# PIPduino.net
KiCad netlist of a schematic drawn in EAGLE
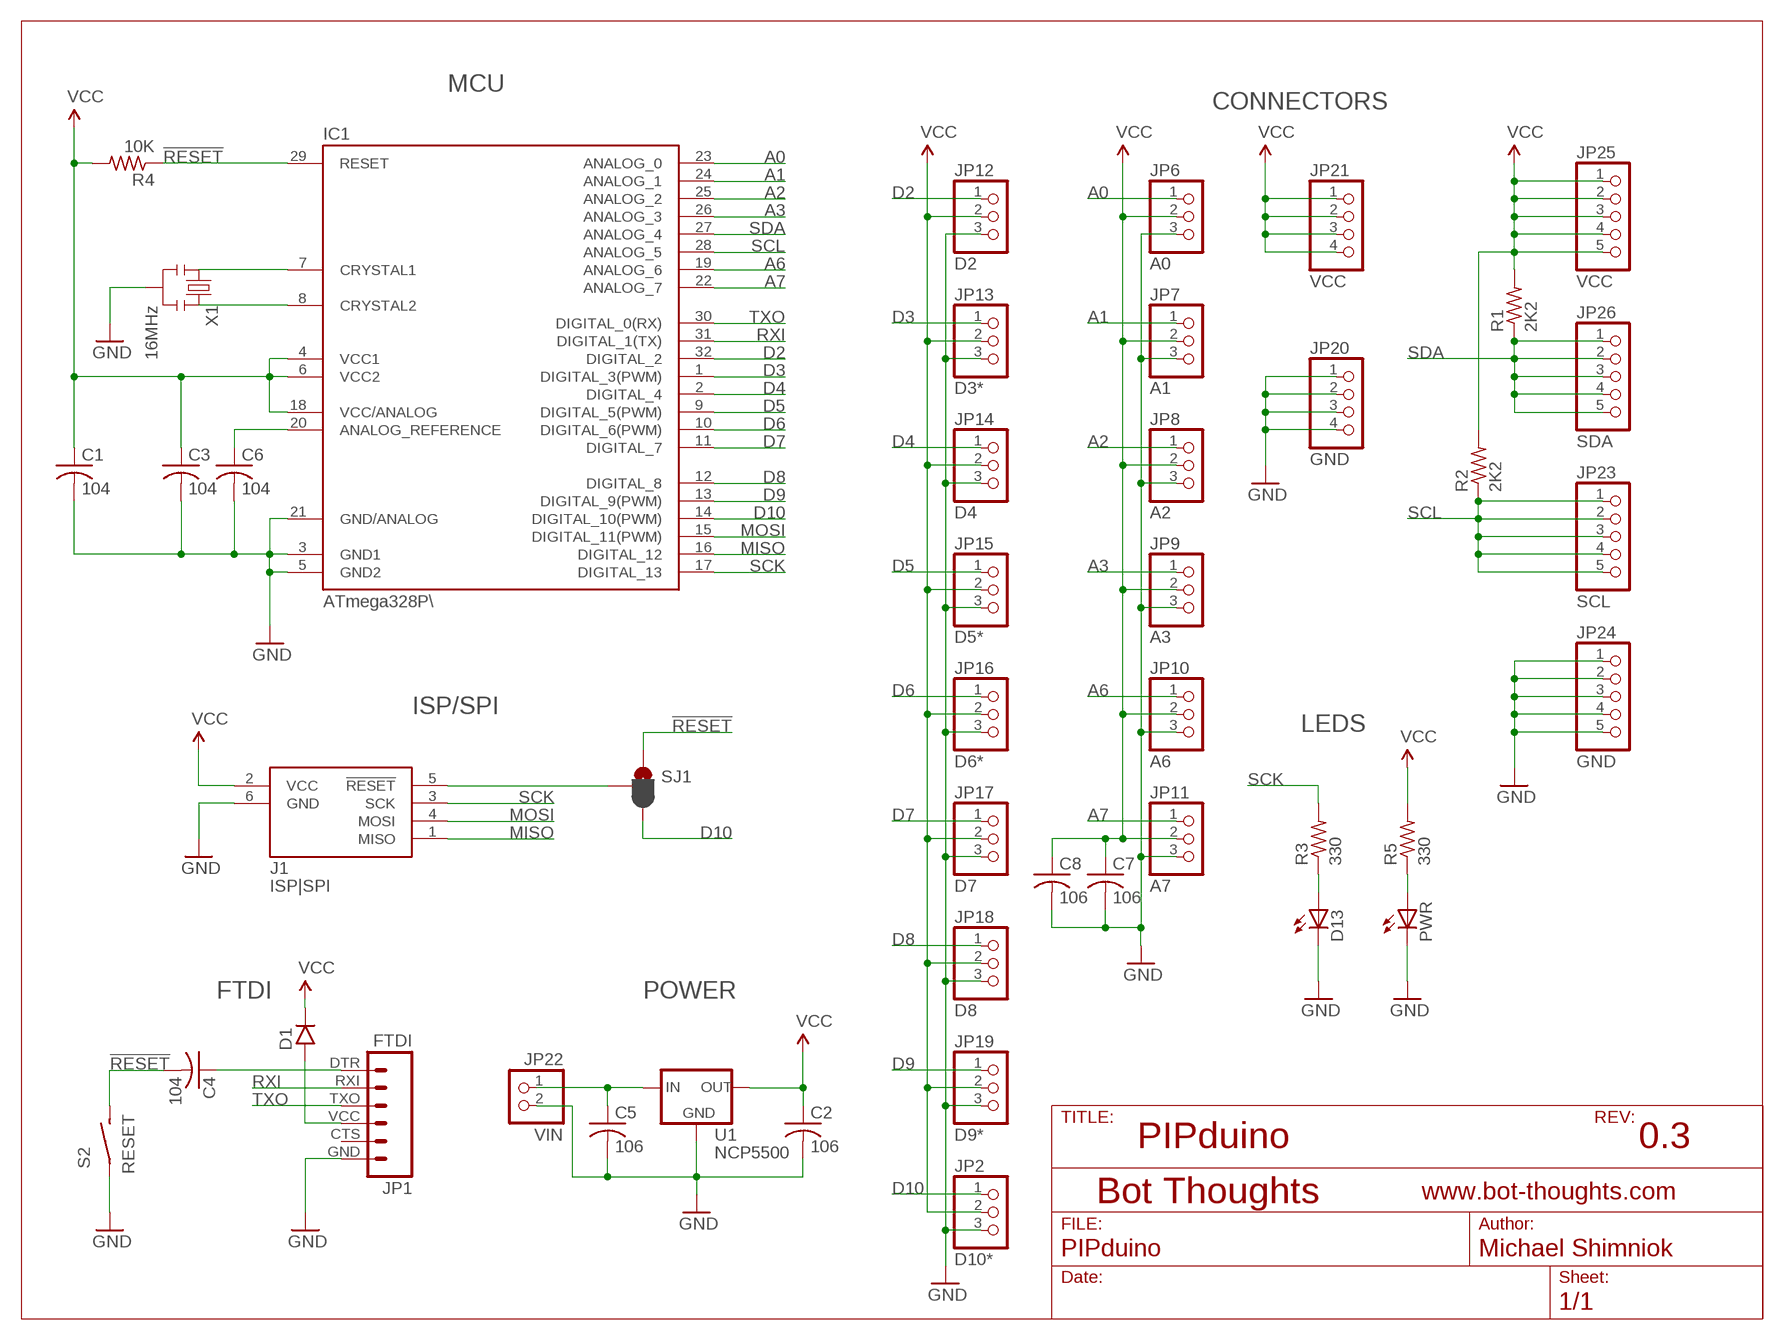
[diagram p0: schematic, sheet 1]

(export (version "E")
  (design (tool "Eeschema 10.0.6"))
  (components
    (comp (ref "C1")
      (value "104")
      (footprint "eagle-import:C0603")
      (libsource (lib "eagle-import") (part "C-USC0603"))
    )
    (comp (ref "C2")
      (value "106")
      (footprint "eagle-import:C1206")
      (libsource (lib "eagle-import") (part "C-USC1206"))
    )
    (comp (ref "C3")
      (value "104")
      (footprint "eagle-import:C0603")
      (libsource (lib "eagle-import") (part "C-USC0603"))
    )
    (comp (ref "C4")
      (value "104")
      (footprint "eagle-import:C0603")
      (libsource (lib "eagle-import") (part "C-USC0603"))
    )
    (comp (ref "C5")
      (value "106")
      (footprint "eagle-import:C1206")
      (libsource (lib "eagle-import") (part "C-USC1206"))
    )
    (comp (ref "C6")
      (value "104")
      (footprint "eagle-import:C0603")
      (libsource (lib "eagle-import") (part "C-USC0603"))
    )
    (comp (ref "C7")
      (value "106")
      (footprint "eagle-import:C1206")
      (libsource (lib "eagle-import") (part "C-USC1206"))
    )
    (comp (ref "C8")
      (value "106")
      (footprint "eagle-import:C1206")
      (libsource (lib "eagle-import") (part "C-USC1206"))
    )
    (comp (ref "D1")
      (value "DIODE_SOD123FL")
      (footprint "eagle-import:SOD123FL")
      (libsource (lib "eagle-import") (part "DIODE_SOD123FL"))
    )
    (comp (ref "D13")
      (value "LED3MM")
      (footprint "eagle-import:LED3MM")
      (libsource (lib "eagle-import") (part "LED3MM"))
    )
    (comp (ref "IC1")
      (value "ATmega328P\\")
      (footprint "eagle-import:TQFP32-08")
      (libsource (lib "eagle-import") (part "ATMEGA168-AU"))
    )
    (comp (ref "J1")
      (value "ISP|SPI")
      (footprint "eagle-import:CON6P2R")
      (libsource (lib "eagle-import") (part "AVRISP6_COMPACT"))
    )
    (comp (ref "JP1")
      (value "FTDI")
      (footprint "eagle-import:FTDI_BASIC")
      (libsource (lib "eagle-import") (part "FTDI_BASICPTH"))
    )
    (comp (ref "JP2")
      (value "D10*")
      (footprint "eagle-import:1X03-S")
      (libsource (lib "eagle-import") (part "PINHD-1X03_2.54-S"))
    )
    (comp (ref "JP6")
      (value "A0")
      (footprint "eagle-import:1X03-S")
      (libsource (lib "eagle-import") (part "PINHD-1X03_2.54-S"))
    )
    (comp (ref "JP7")
      (value "A1")
      (footprint "eagle-import:1X03-S")
      (libsource (lib "eagle-import") (part "PINHD-1X03_2.54-S"))
    )
    (comp (ref "JP8")
      (value "A2")
      (footprint "eagle-import:1X03-S")
      (libsource (lib "eagle-import") (part "PINHD-1X03_2.54-S"))
    )
    (comp (ref "JP9")
      (value "A3")
      (footprint "eagle-import:1X03-S")
      (libsource (lib "eagle-import") (part "PINHD-1X03_2.54-S"))
    )
    (comp (ref "JP10")
      (value "A6")
      (footprint "eagle-import:1X03-S")
      (libsource (lib "eagle-import") (part "PINHD-1X03_2.54-S"))
    )
    (comp (ref "JP11")
      (value "A7")
      (footprint "eagle-import:1X03-S")
      (libsource (lib "eagle-import") (part "PINHD-1X03_2.54-S"))
    )
    (comp (ref "JP12")
      (value "D2")
      (footprint "eagle-import:1X03-S")
      (libsource (lib "eagle-import") (part "PINHD-1X03_2.54-S"))
    )
    (comp (ref "JP13")
      (value "D3*")
      (footprint "eagle-import:1X03-S")
      (libsource (lib "eagle-import") (part "PINHD-1X03_2.54-S"))
    )
    (comp (ref "JP14")
      (value "D4")
      (footprint "eagle-import:1X03-S")
      (libsource (lib "eagle-import") (part "PINHD-1X03_2.54-S"))
    )
    (comp (ref "JP15")
      (value "D5*")
      (footprint "eagle-import:1X03-S")
      (libsource (lib "eagle-import") (part "PINHD-1X03_2.54-S"))
    )
    (comp (ref "JP16")
      (value "D6*")
      (footprint "eagle-import:1X03-S")
      (libsource (lib "eagle-import") (part "PINHD-1X03_2.54-S"))
    )
    (comp (ref "JP17")
      (value "D7")
      (footprint "eagle-import:1X03-S")
      (libsource (lib "eagle-import") (part "PINHD-1X03_2.54-S"))
    )
    (comp (ref "JP18")
      (value "D8")
      (footprint "eagle-import:1X03-S")
      (libsource (lib "eagle-import") (part "PINHD-1X03_2.54-S"))
    )
    (comp (ref "JP19")
      (value "D9*")
      (footprint "eagle-import:1X03-S")
      (libsource (lib "eagle-import") (part "PINHD-1X03_2.54-S"))
    )
    (comp (ref "JP20")
      (value "GND")
      (footprint "eagle-import:1X04-S")
      (libsource (lib "eagle-import") (part "PINHD-1X04_2.54-S"))
    )
    (comp (ref "JP21")
      (value "VCC")
      (footprint "eagle-import:1X04-S")
      (libsource (lib "eagle-import") (part "PINHD-1X04_2.54-S"))
    )
    (comp (ref "JP22")
      (value "VIN")
      (footprint "eagle-import:1X02-S")
      (libsource (lib "eagle-import") (part "PINHD-1X02_2.54-S"))
    )
    (comp (ref "JP23")
      (value "SCL")
      (footprint "eagle-import:1X05-S")
      (libsource (lib "eagle-import") (part "PINHD-1X05_2.54-S"))
    )
    (comp (ref "JP24")
      (value "GND")
      (footprint "eagle-import:1X05-S")
      (libsource (lib "eagle-import") (part "PINHD-1X05_2.54-S"))
    )
    (comp (ref "JP25")
      (value "VCC")
      (footprint "eagle-import:1X05-S")
      (libsource (lib "eagle-import") (part "PINHD-1X05_2.54-S"))
    )
    (comp (ref "JP26")
      (value "SDA")
      (footprint "eagle-import:1X05-S")
      (libsource (lib "eagle-import") (part "PINHD-1X05_2.54-S"))
    )
    (comp (ref "PWR")
      (value "LED3MM")
      (footprint "eagle-import:LED3MM")
      (libsource (lib "eagle-import") (part "LED3MM"))
    )
    (comp (ref "R1")
      (value "2K2")
      (footprint "eagle-import:R0603")
      (libsource (lib "eagle-import") (part "R-US_R0603"))
    )
    (comp (ref "R2")
      (value "2K2")
      (footprint "eagle-import:R0603")
      (libsource (lib "eagle-import") (part "R-US_R0603"))
    )
    (comp (ref "R3")
      (value "330")
      (footprint "eagle-import:R0603")
      (libsource (lib "eagle-import") (part "R-US_R0603"))
    )
    (comp (ref "R4")
      (value "10K")
      (footprint "eagle-import:R0603")
      (libsource (lib "eagle-import") (part "R-US_R0603"))
    )
    (comp (ref "R5")
      (value "330")
      (footprint "eagle-import:R0603")
      (libsource (lib "eagle-import") (part "R-US_R0603"))
    )
    (comp (ref "S2")
      (value "RESET")
      (footprint "eagle-import:3X4X2TACT")
      (libsource (lib "eagle-import") (part "SPST_3X4X2"))
    )
    (comp (ref "SJ1")
      (value "JUMPER-PAD-3-2OF3_NC_BY_PASTE")
      (footprint "eagle-import:PAD-JUMPER-3-2OF3_NC_BY_PASTE_YES_SILK_FULL_BOX")
      (libsource (lib "eagle-import") (part "JUMPER-PAD-3-2OF3_NC_BY_PASTE"))
    )
    (comp (ref "U1")
      (value "NCP5500")
      (footprint "eagle-import:DPAK")
      (libsource (lib "eagle-import") (part "NCP5500"))
    )
    (comp (ref "X1")
      (value "16MHz")
      (footprint "eagle-import:CSTCE_V_C")
      (libsource (lib "eagle-import") (part "RESONATOR_CSTCE_V_C"))
    )
  )
  (nets
    (net (code "1") (name "/A0") (class "Default")
      (node (ref "IC1") (pin "23") (pinfunction "ANALOG_0_23") (pintype "bidirectional"))
      (node (ref "JP6") (pin "1") (pinfunction "1_1") (pintype "passive"))
    )
    (net (code "2") (name "/A1") (class "Default")
      (node (ref "IC1") (pin "24") (pinfunction "ANALOG_1_24") (pintype "bidirectional"))
      (node (ref "JP7") (pin "1") (pinfunction "1_1") (pintype "passive"))
    )
    (net (code "3") (name "/A2") (class "Default")
      (node (ref "IC1") (pin "25") (pinfunction "ANALOG_2_25") (pintype "bidirectional"))
      (node (ref "JP8") (pin "1") (pinfunction "1_1") (pintype "passive"))
    )
    (net (code "4") (name "/A3") (class "Default")
      (node (ref "IC1") (pin "26") (pinfunction "ANALOG_3_26") (pintype "bidirectional"))
      (node (ref "JP9") (pin "1") (pinfunction "1_1") (pintype "passive"))
    )
    (net (code "5") (name "/A6") (class "Default")
      (node (ref "IC1") (pin "19") (pinfunction "ANALOG_6_19") (pintype "passive"))
      (node (ref "JP10") (pin "1") (pinfunction "1_1") (pintype "passive"))
    )
    (net (code "6") (name "/A7") (class "Default")
      (node (ref "IC1") (pin "22") (pinfunction "ANALOG_7_22") (pintype "passive"))
      (node (ref "JP11") (pin "1") (pinfunction "1_1") (pintype "passive"))
    )
    (net (code "7") (name "/D2") (class "Default")
      (node (ref "IC1") (pin "32") (pinfunction "DIGITAL_2_32") (pintype "bidirectional"))
      (node (ref "JP12") (pin "1") (pinfunction "1_1") (pintype "passive"))
    )
    (net (code "8") (name "/D3") (class "Default")
      (node (ref "IC1") (pin "1") (pinfunction "DIGITAL_3(PWM)_1") (pintype "bidirectional"))
      (node (ref "JP13") (pin "1") (pinfunction "1_1") (pintype "passive"))
    )
    (net (code "9") (name "/D4") (class "Default")
      (node (ref "IC1") (pin "2") (pinfunction "DIGITAL_4_2") (pintype "bidirectional"))
      (node (ref "JP14") (pin "1") (pinfunction "1_1") (pintype "passive"))
    )
    (net (code "10") (name "/D5") (class "Default")
      (node (ref "IC1") (pin "9") (pinfunction "DIGITAL_5(PWM)_9") (pintype "bidirectional"))
      (node (ref "JP15") (pin "1") (pinfunction "1_1") (pintype "passive"))
    )
    (net (code "11") (name "/D6") (class "Default")
      (node (ref "IC1") (pin "10") (pinfunction "DIGITAL_6(PWM)_10") (pintype "bidirectional"))
      (node (ref "JP16") (pin "1") (pinfunction "1_1") (pintype "passive"))
    )
    (net (code "12") (name "/D7") (class "Default")
      (node (ref "IC1") (pin "11") (pinfunction "DIGITAL_7_11") (pintype "bidirectional"))
      (node (ref "JP17") (pin "1") (pinfunction "1_1") (pintype "passive"))
    )
    (net (code "13") (name "/D8") (class "Default")
      (node (ref "IC1") (pin "12") (pinfunction "DIGITAL_8_12") (pintype "bidirectional"))
      (node (ref "JP18") (pin "1") (pinfunction "1_1") (pintype "passive"))
    )
    (net (code "14") (name "/D9") (class "Default")
      (node (ref "IC1") (pin "13") (pinfunction "DIGITAL_9(PWM)_13") (pintype "bidirectional"))
      (node (ref "JP19") (pin "1") (pinfunction "1_1") (pintype "passive"))
    )
    (net (code "15") (name "/D10") (class "Default")
      (node (ref "IC1") (pin "14") (pinfunction "DIGITAL_10(PWM)_14") (pintype "bidirectional"))
      (node (ref "JP2") (pin "1") (pinfunction "1_1") (pintype "passive"))
      (node (ref "SJ1") (pin "3") (pinfunction "3_3") (pintype "passive"))
    )
    (net (code "16") (name "/MISO") (class "Default")
      (node (ref "IC1") (pin "16") (pinfunction "DIGITAL_12_16") (pintype "bidirectional"))
      (node (ref "J1") (pin "1") (pinfunction "MISO_1") (pintype "input"))
    )
    (net (code "17") (name "/MOSI") (class "Default")
      (node (ref "IC1") (pin "15") (pinfunction "DIGITAL_11(PWM)_15") (pintype "bidirectional"))
      (node (ref "J1") (pin "4") (pinfunction "MOSI_4") (pintype "output"))
    )
    (net (code "18") (name "/RXI") (class "Default")
      (node (ref "IC1") (pin "31") (pinfunction "DIGITAL_1(TX)_31") (pintype "bidirectional"))
      (node (ref "JP1") (pin "RXI") (pinfunction "2_RXI") (pintype "passive"))
    )
    (net (code "19") (name "/SCK") (class "Default")
      (node (ref "IC1") (pin "17") (pinfunction "DIGITAL_13_17") (pintype "bidirectional"))
      (node (ref "J1") (pin "3") (pinfunction "SCK_3") (pintype "output"))
      (node (ref "R3") (pin "2") (pinfunction "2_2") (pintype "passive"))
    )
    (net (code "20") (name "/SCL") (class "Default")
      (node (ref "IC1") (pin "28") (pinfunction "ANALOG_5_28") (pintype "bidirectional"))
      (node (ref "JP23") (pin "1") (pinfunction "1_1") (pintype "passive"))
      (node (ref "JP23") (pin "2") (pinfunction "2_2") (pintype "passive"))
      (node (ref "JP23") (pin "3") (pinfunction "3_3") (pintype "passive"))
      (node (ref "JP23") (pin "4") (pinfunction "4_4") (pintype "passive"))
      (node (ref "JP23") (pin "5") (pinfunction "5_5") (pintype "passive"))
      (node (ref "R2") (pin "1") (pinfunction "1_1") (pintype "passive"))
    )
    (net (code "21") (name "/SDA") (class "Default")
      (node (ref "IC1") (pin "27") (pinfunction "ANALOG_4_27") (pintype "bidirectional"))
      (node (ref "JP26") (pin "1") (pinfunction "1_1") (pintype "passive"))
      (node (ref "JP26") (pin "2") (pinfunction "2_2") (pintype "passive"))
      (node (ref "JP26") (pin "3") (pinfunction "3_3") (pintype "passive"))
      (node (ref "JP26") (pin "4") (pinfunction "4_4") (pintype "passive"))
      (node (ref "JP26") (pin "5") (pinfunction "5_5") (pintype "passive"))
      (node (ref "R1") (pin "1") (pinfunction "1_1") (pintype "passive"))
    )
    (net (code "22") (name "/TXO") (class "Default")
      (node (ref "IC1") (pin "30") (pinfunction "DIGITAL_0(RX)_30") (pintype "bidirectional"))
      (node (ref "JP1") (pin "TXO") (pinfunction "3_TXO") (pintype "passive"))
    )
    (net (code "23") (name "/~{RESET}") (class "Default")
      (node (ref "C4") (pin "2") (pinfunction "2_2") (pintype "passive"))
      (node (ref "IC1") (pin "29") (pinfunction "RESET_29") (pintype "bidirectional"))
      (node (ref "R4") (pin "1") (pinfunction "1_1") (pintype "passive"))
      (node (ref "S2") (pin "P$2") (pinfunction "S_P$2") (pintype "passive"))
      (node (ref "SJ1") (pin "1") (pinfunction "1_1") (pintype "passive"))
    )
    (net (code "24") (name "GND") (class "Default")
      (node (ref "C1") (pin "2") (pinfunction "2_2") (pintype "passive"))
      (node (ref "C2") (pin "2") (pinfunction "2_2") (pintype "passive"))
      (node (ref "C3") (pin "2") (pinfunction "2_2") (pintype "passive"))
      (node (ref "C5") (pin "2") (pinfunction "2_2") (pintype "passive"))
      (node (ref "C6") (pin "2") (pinfunction "2_2") (pintype "passive"))
      (node (ref "C7") (pin "2") (pinfunction "2_2") (pintype "passive"))
      (node (ref "C8") (pin "2") (pinfunction "2_2") (pintype "passive"))
      (node (ref "D13") (pin "K") (pinfunction "C_K") (pintype "passive"))
      (node (ref "IC1") (pin "21") (pinfunction "GND/ANALOG_21") (pintype "power_in"))
      (node (ref "IC1") (pin "3") (pinfunction "GND1_3") (pintype "power_in"))
      (node (ref "IC1") (pin "5") (pinfunction "GND2_5") (pintype "power_in"))
      (node (ref "J1") (pin "6") (pinfunction "GND_6") (pintype "power_in"))
      (node (ref "JP1") (pin "GND") (pinfunction "6_GND") (pintype "passive"))
      (node (ref "JP10") (pin "3") (pinfunction "3_3") (pintype "passive"))
      (node (ref "JP11") (pin "3") (pinfunction "3_3") (pintype "passive"))
      (node (ref "JP12") (pin "3") (pinfunction "3_3") (pintype "passive"))
      (node (ref "JP13") (pin "3") (pinfunction "3_3") (pintype "passive"))
      (node (ref "JP14") (pin "3") (pinfunction "3_3") (pintype "passive"))
      (node (ref "JP15") (pin "3") (pinfunction "3_3") (pintype "passive"))
      (node (ref "JP16") (pin "3") (pinfunction "3_3") (pintype "passive"))
      (node (ref "JP17") (pin "3") (pinfunction "3_3") (pintype "passive"))
      (node (ref "JP18") (pin "3") (pinfunction "3_3") (pintype "passive"))
      (node (ref "JP19") (pin "3") (pinfunction "3_3") (pintype "passive"))
      (node (ref "JP2") (pin "3") (pinfunction "3_3") (pintype "passive"))
      (node (ref "JP20") (pin "1") (pinfunction "1_1") (pintype "passive"))
      (node (ref "JP20") (pin "2") (pinfunction "2_2") (pintype "passive"))
      (node (ref "JP20") (pin "3") (pinfunction "3_3") (pintype "passive"))
      (node (ref "JP20") (pin "4") (pinfunction "4_4") (pintype "passive"))
      (node (ref "JP22") (pin "2") (pinfunction "2_2") (pintype "passive"))
      (node (ref "JP24") (pin "1") (pinfunction "1_1") (pintype "passive"))
      (node (ref "JP24") (pin "2") (pinfunction "2_2") (pintype "passive"))
      (node (ref "JP24") (pin "3") (pinfunction "3_3") (pintype "passive"))
      (node (ref "JP24") (pin "4") (pinfunction "4_4") (pintype "passive"))
      (node (ref "JP24") (pin "5") (pinfunction "5_5") (pintype "passive"))
      (node (ref "JP6") (pin "3") (pinfunction "3_3") (pintype "passive"))
      (node (ref "JP7") (pin "3") (pinfunction "3_3") (pintype "passive"))
      (node (ref "JP8") (pin "3") (pinfunction "3_3") (pintype "passive"))
      (node (ref "JP9") (pin "3") (pinfunction "3_3") (pintype "passive"))
      (node (ref "PWR") (pin "K") (pinfunction "C_K") (pintype "passive"))
      (node (ref "S2") (pin "P$1") (pinfunction "P_P$1") (pintype "passive"))
      (node (ref "U1") (pin "4") (pinfunction "GND_4") (pintype "bidirectional"))
      (node (ref "X1") (pin "GND") (pinfunction "GND_GND") (pintype "passive"))
    )
    (net (code "25") (name "Net-(D13-PadA)") (class "Default")
      (node (ref "D13") (pin "A") (pinfunction "A_A") (pintype "passive"))
      (node (ref "R3") (pin "1") (pinfunction "1_1") (pintype "passive"))
    )
    (net (code "26") (name "Net-(IC1-ANALOG_REFERENCE)") (class "Default")
      (node (ref "C6") (pin "1") (pinfunction "1_1") (pintype "passive"))
      (node (ref "IC1") (pin "20") (pinfunction "ANALOG_REFERENCE_20") (pintype "passive"))
    )
    (net (code "27") (name "Net-(IC1-CRYSTAL1)") (class "Default")
      (node (ref "IC1") (pin "7") (pinfunction "CRYSTAL1_7") (pintype "bidirectional"))
      (node (ref "X1") (pin "X1") (pinfunction "X1_X1") (pintype "passive"))
    )
    (net (code "28") (name "Net-(IC1-CRYSTAL2)") (class "Default")
      (node (ref "IC1") (pin "8") (pinfunction "CRYSTAL2_8") (pintype "bidirectional"))
      (node (ref "X1") (pin "X2") (pinfunction "X2_X2") (pintype "passive"))
    )
    (net (code "29") (name "Net-(J1-~{RESET})") (class "Default")
      (node (ref "J1") (pin "5") (pinfunction "~{RESET}_5") (pintype "output"))
      (node (ref "SJ1") (pin "2") (pinfunction "2_2") (pintype "passive"))
    )
    (net (code "30") (name "Net-(JP1-1)") (class "Default")
      (node (ref "C4") (pin "1") (pinfunction "1_1") (pintype "passive"))
      (node (ref "JP1") (pin "DTR") (pinfunction "1_DTR") (pintype "passive"))
    )
    (net (code "31") (name "Net-(JP1-4)") (class "Default")
      (node (ref "D1") (pin "A") (pinfunction "A_A") (pintype "passive"))
      (node (ref "JP1") (pin "VCC") (pinfunction "4_VCC") (pintype "passive"))
    )
    (net (code "32") (name "Net-(PWR-PadA)") (class "Default")
      (node (ref "PWR") (pin "A") (pinfunction "A_A") (pintype "passive"))
      (node (ref "R5") (pin "1") (pinfunction "1_1") (pintype "passive"))
    )
    (net (code "33") (name "Net-(U1-VIN)") (class "Default")
      (node (ref "C5") (pin "1") (pinfunction "1_1") (pintype "passive"))
      (node (ref "JP22") (pin "1") (pinfunction "1_1") (pintype "passive"))
      (node (ref "U1") (pin "1") (pinfunction "VIN_1") (pintype "bidirectional"))
    )
    (net (code "34") (name "VCC") (class "Default")
      (node (ref "C1") (pin "1") (pinfunction "1_1") (pintype "passive"))
      (node (ref "C2") (pin "1") (pinfunction "1_1") (pintype "passive"))
      (node (ref "C3") (pin "1") (pinfunction "1_1") (pintype "passive"))
      (node (ref "C7") (pin "1") (pinfunction "1_1") (pintype "passive"))
      (node (ref "C8") (pin "1") (pinfunction "1_1") (pintype "passive"))
      (node (ref "D1") (pin "C") (pinfunction "C_C") (pintype "passive"))
      (node (ref "IC1") (pin "18") (pinfunction "VCC/ANALOG_18") (pintype "passive"))
      (node (ref "IC1") (pin "4") (pinfunction "VCC1_4") (pintype "power_in"))
      (node (ref "IC1") (pin "6") (pinfunction "VCC2_6") (pintype "power_in"))
      (node (ref "J1") (pin "2") (pinfunction "VCC_2") (pintype "power_in"))
      (node (ref "JP10") (pin "2") (pinfunction "2_2") (pintype "passive"))
      (node (ref "JP11") (pin "2") (pinfunction "2_2") (pintype "passive"))
      (node (ref "JP12") (pin "2") (pinfunction "2_2") (pintype "passive"))
      (node (ref "JP13") (pin "2") (pinfunction "2_2") (pintype "passive"))
      (node (ref "JP14") (pin "2") (pinfunction "2_2") (pintype "passive"))
      (node (ref "JP15") (pin "2") (pinfunction "2_2") (pintype "passive"))
      (node (ref "JP16") (pin "2") (pinfunction "2_2") (pintype "passive"))
      (node (ref "JP17") (pin "2") (pinfunction "2_2") (pintype "passive"))
      (node (ref "JP18") (pin "2") (pinfunction "2_2") (pintype "passive"))
      (node (ref "JP19") (pin "2") (pinfunction "2_2") (pintype "passive"))
      (node (ref "JP2") (pin "2") (pinfunction "2_2") (pintype "passive"))
      (node (ref "JP21") (pin "1") (pinfunction "1_1") (pintype "passive"))
      (node (ref "JP21") (pin "2") (pinfunction "2_2") (pintype "passive"))
      (node (ref "JP21") (pin "3") (pinfunction "3_3") (pintype "passive"))
      (node (ref "JP21") (pin "4") (pinfunction "4_4") (pintype "passive"))
      (node (ref "JP25") (pin "1") (pinfunction "1_1") (pintype "passive"))
      (node (ref "JP25") (pin "2") (pinfunction "2_2") (pintype "passive"))
      (node (ref "JP25") (pin "3") (pinfunction "3_3") (pintype "passive"))
      (node (ref "JP25") (pin "4") (pinfunction "4_4") (pintype "passive"))
      (node (ref "JP25") (pin "5") (pinfunction "5_5") (pintype "passive"))
      (node (ref "JP6") (pin "2") (pinfunction "2_2") (pintype "passive"))
      (node (ref "JP7") (pin "2") (pinfunction "2_2") (pintype "passive"))
      (node (ref "JP8") (pin "2") (pinfunction "2_2") (pintype "passive"))
      (node (ref "JP9") (pin "2") (pinfunction "2_2") (pintype "passive"))
      (node (ref "R1") (pin "2") (pinfunction "2_2") (pintype "passive"))
      (node (ref "R2") (pin "2") (pinfunction "2_2") (pintype "passive"))
      (node (ref "R4") (pin "2") (pinfunction "2_2") (pintype "passive"))
      (node (ref "R5") (pin "2") (pinfunction "2_2") (pintype "passive"))
      (node (ref "U1") (pin "3") (pinfunction "VOUT_3") (pintype "bidirectional"))
    )
    (net (code "35") (name "unconnected-(JP1-5-PadCTS)") (class "Default")
      (node (ref "JP1") (pin "CTS") (pinfunction "5_CTS") (pintype "passive"))
    )
  )
)
